# EXTERNAL_BME280.net
KiCad netlist of a schematic drawn in EAGLE
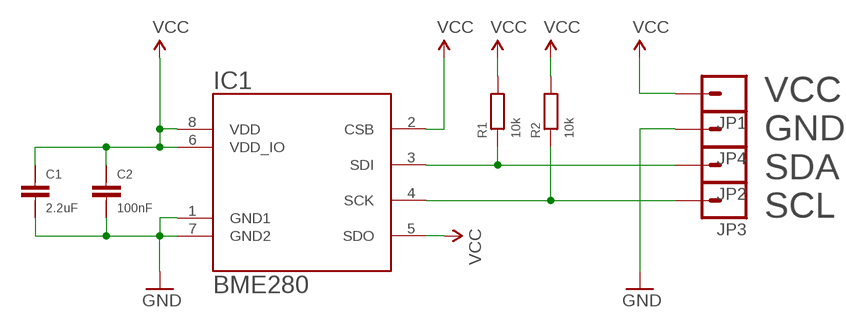
[diagram p0: schematic, sheet 1]

(export (version "E")
  (design (tool "Eeschema 10.0.6"))
  (components
    (comp (ref "C1")
      (value "2.2uF")
      (footprint "eagle-import:0402")
      (libsource (lib "eagle-import") (part "CAP-0402"))
    )
    (comp (ref "C2")
      (value "100nF")
      (footprint "eagle-import:0402")
      (libsource (lib "eagle-import") (part "CAP-0402"))
    )
    (comp (ref "IC1")
      (value "BME280")
      (footprint "eagle-import:BME280")
      (libsource (lib "eagle-import") (part "BME280"))
    )
    (comp (ref "JP1")
      (value "M01SOLAR")
      (footprint "eagle-import:PAD2_1.8X0.9")
      (libsource (lib "eagle-import") (part "M01SOLAR"))
    )
    (comp (ref "JP2")
      (value "M01SOLAR")
      (footprint "eagle-import:PAD2_1.8X0.9")
      (libsource (lib "eagle-import") (part "M01SOLAR"))
    )
    (comp (ref "JP3")
      (value "M01SOLAR")
      (footprint "eagle-import:PAD2_1.8X0.9")
      (libsource (lib "eagle-import") (part "M01SOLAR"))
    )
    (comp (ref "JP4")
      (value "M01SOLAR")
      (footprint "eagle-import:PAD2_1.8X0.9")
      (libsource (lib "eagle-import") (part "M01SOLAR"))
    )
    (comp (ref "R1")
      (value "10k")
      (footprint "eagle-import:0402")
      (libsource (lib "eagle-import") (part "RES-0402"))
    )
    (comp (ref "R2")
      (value "10k")
      (footprint "eagle-import:0402")
      (libsource (lib "eagle-import") (part "RES-0402"))
    )
  )
  (nets
    (net (code "1") (name "GND") (class "Default")
      (node (ref "C1") (pin "P$1") (pinfunction "1_P$1") (pintype "passive"))
      (node (ref "C2") (pin "P$1") (pinfunction "1_P$1") (pintype "passive"))
      (node (ref "IC1") (pin "1") (pinfunction "GND1_1") (pintype "bidirectional"))
      (node (ref "IC1") (pin "7") (pinfunction "GND2_7") (pintype "bidirectional"))
      (node (ref "JP4") (pin "1") (pinfunction "1_1") (pintype "passive"))
    )
    (net (code "2") (name "Net-(IC1-SCK)") (class "Default")
      (node (ref "IC1") (pin "4") (pinfunction "SCK_4") (pintype "bidirectional"))
      (node (ref "JP3") (pin "1") (pinfunction "1_1") (pintype "passive"))
      (node (ref "R2") (pin "P$1") (pinfunction "1_P$1") (pintype "passive"))
    )
    (net (code "3") (name "Net-(IC1-SDI)") (class "Default")
      (node (ref "IC1") (pin "3") (pinfunction "SDI_3") (pintype "bidirectional"))
      (node (ref "JP2") (pin "1") (pinfunction "1_1") (pintype "passive"))
      (node (ref "R1") (pin "P$1") (pinfunction "1_P$1") (pintype "passive"))
    )
    (net (code "4") (name "VCC") (class "Default")
      (node (ref "C1") (pin "P$2") (pinfunction "2_P$2") (pintype "passive"))
      (node (ref "C2") (pin "P$2") (pinfunction "2_P$2") (pintype "passive"))
      (node (ref "IC1") (pin "2") (pinfunction "CSB_2") (pintype "bidirectional"))
      (node (ref "IC1") (pin "5") (pinfunction "SDO_5") (pintype "bidirectional"))
      (node (ref "IC1") (pin "6") (pinfunction "VDD_IO_6") (pintype "bidirectional"))
      (node (ref "IC1") (pin "8") (pinfunction "VDD_8") (pintype "bidirectional"))
      (node (ref "JP1") (pin "1") (pinfunction "1_1") (pintype "passive"))
      (node (ref "R1") (pin "P$2") (pinfunction "2_P$2") (pintype "passive"))
      (node (ref "R2") (pin "P$2") (pinfunction "2_P$2") (pintype "passive"))
    )
  )
)
